# DPA110_to-264v4-upravena.net
KiCad netlist of a schematic drawn in EAGLE
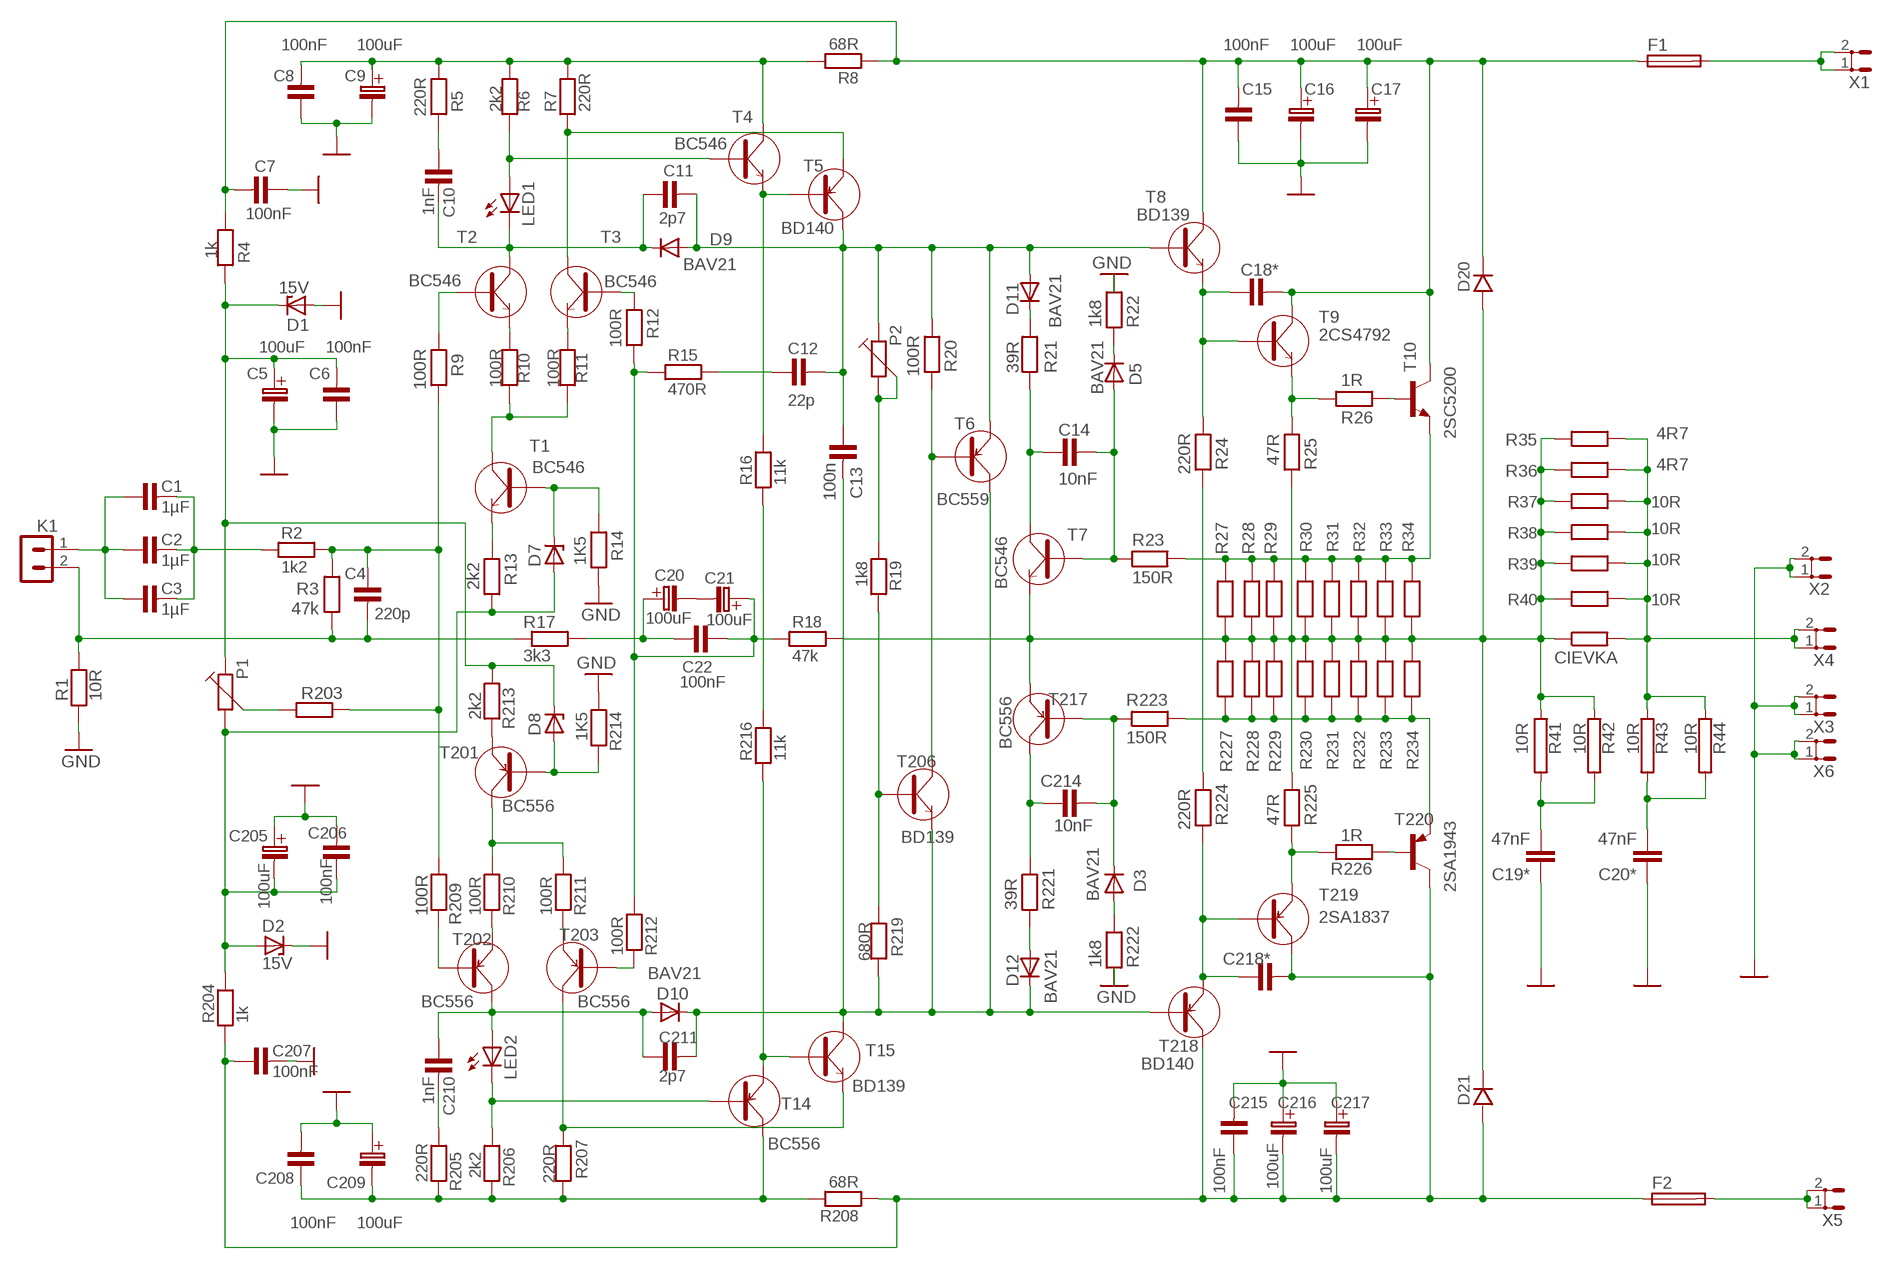
[diagram p0: schematic, sheet 1]

(export (version "E")
  (design (tool "Eeschema 10.0.6"))
  (components
    (comp (ref "C1")
      (value "1µF")
      (footprint "eagle-import:C-5")
      (libsource (lib "eagle-import") (part "C-KERAMIK_5"))
    )
    (comp (ref "C2")
      (value "1µF")
      (footprint "eagle-import:C-5")
      (libsource (lib "eagle-import") (part "C-KERAMIK_5"))
    )
    (comp (ref "C3")
      (value "1µF")
      (footprint "eagle-import:C-5")
      (libsource (lib "eagle-import") (part "C-KERAMIK_5"))
    )
    (comp (ref "C4")
      (value "220p")
      (footprint "eagle-import:C-5")
      (libsource (lib "eagle-import") (part "C-KERAMIK_5"))
    )
    (comp (ref "C5")
      (value "100uF")
      (footprint "eagle-import:C-EL_2")
      (libsource (lib "eagle-import") (part "C-ELEKTROLYT_2"))
    )
    (comp (ref "C6")
      (value "100nF")
      (footprint "eagle-import:C-5")
      (libsource (lib "eagle-import") (part "C-KERAMIK_5"))
    )
    (comp (ref "C7")
      (value "100nF")
      (footprint "eagle-import:C-5")
      (libsource (lib "eagle-import") (part "C-KERAMIK_5"))
    )
    (comp (ref "C8")
      (value "100nF")
      (footprint "eagle-import:C-5")
      (libsource (lib "eagle-import") (part "C-KERAMIK_5"))
    )
    (comp (ref "C9")
      (value "100uF")
      (footprint "eagle-import:C-EL_3,5")
      (libsource (lib "eagle-import") (part "C-ELEKTROLYT_3,5"))
    )
    (comp (ref "C10")
      (value "1nF")
      (footprint "eagle-import:C-5")
      (libsource (lib "eagle-import") (part "#PaJa_30_C-KERAMIK_5"))
    )
    (comp (ref "C11")
      (value "2p7")
      (footprint "eagle-import:C-5")
      (libsource (lib "eagle-import") (part "C-KERAMIK_5"))
    )
    (comp (ref "C12")
      (value "22p")
      (footprint "eagle-import:C-5")
      (libsource (lib "eagle-import") (part "C-KERAMIK_5"))
    )
    (comp (ref "C13")
      (value "100n")
      (footprint "eagle-import:C-5")
      (libsource (lib "eagle-import") (part "C-KERAMIK_5"))
    )
    (comp (ref "C14")
      (value "10nF")
      (footprint "eagle-import:C-5")
      (libsource (lib "eagle-import") (part "C-KERAMIK_5"))
    )
    (comp (ref "C15")
      (value "100nF")
      (footprint "eagle-import:C-5")
      (libsource (lib "eagle-import") (part "C-KERAMIK_5"))
    )
    (comp (ref "C16")
      (value "100uF")
      (footprint "eagle-import:C-EL_3,5")
      (libsource (lib "eagle-import") (part "C-ELEKTROLYT_3,5"))
    )
    (comp (ref "C17")
      (value "100uF")
      (footprint "eagle-import:C-EL_3,5")
      (libsource (lib "eagle-import") (part "C-ELEKTROLYT_3,5"))
    )
    (comp (ref "C18*")
      (value "C-KERAMIK_5")
      (footprint "eagle-import:C-5")
      (libsource (lib "eagle-import") (part "C-KERAMIK_5"))
    )
    (comp (ref "C19*")
      (value "47nF")
      (footprint "eagle-import:C150-054X183")
      (libsource (lib "eagle-import") (part "C-EU150-054X183"))
    )
    (comp (ref "C20")
      (value "100uF")
      (footprint "eagle-import:C-EL_3,5")
      (libsource (lib "eagle-import") (part "C-ELEKTROLYT_3,5"))
    )
    (comp (ref "C20*")
      (value "47nF")
      (footprint "eagle-import:C150-054X183")
      (libsource (lib "eagle-import") (part "C-EU150-054X183"))
    )
    (comp (ref "C21")
      (value "100uF")
      (footprint "eagle-import:C-EL_3,5")
      (libsource (lib "eagle-import") (part "C-ELEKTROLYT_3,5"))
    )
    (comp (ref "C22")
      (value "100nF")
      (footprint "eagle-import:C-5")
      (libsource (lib "eagle-import") (part "C-KERAMIK_5"))
    )
    (comp (ref "C205")
      (value "100uF")
      (footprint "eagle-import:C-EL_2")
      (libsource (lib "eagle-import") (part "C-ELEKTROLYT_2"))
    )
    (comp (ref "C206")
      (value "100nF")
      (footprint "eagle-import:C-5")
      (libsource (lib "eagle-import") (part "C-KERAMIK_5"))
    )
    (comp (ref "C207")
      (value "100nF")
      (footprint "eagle-import:C-5")
      (libsource (lib "eagle-import") (part "C-KERAMIK_5"))
    )
    (comp (ref "C208")
      (value "100nF")
      (footprint "eagle-import:C-5")
      (libsource (lib "eagle-import") (part "C-KERAMIK_5"))
    )
    (comp (ref "C209")
      (value "100uF")
      (footprint "eagle-import:C-EL_3,5")
      (libsource (lib "eagle-import") (part "C-ELEKTROLYT_3,5"))
    )
    (comp (ref "C210")
      (value "1nF")
      (footprint "eagle-import:C-5")
      (libsource (lib "eagle-import") (part "#PaJa_30_C-KERAMIK_5"))
    )
    (comp (ref "C211")
      (value "2p7")
      (footprint "eagle-import:C-5")
      (libsource (lib "eagle-import") (part "C-KERAMIK_5"))
    )
    (comp (ref "C214")
      (value "10nF")
      (footprint "eagle-import:C-5")
      (libsource (lib "eagle-import") (part "C-KERAMIK_5"))
    )
    (comp (ref "C215")
      (value "100nF")
      (footprint "eagle-import:C-5")
      (libsource (lib "eagle-import") (part "C-KERAMIK_5"))
    )
    (comp (ref "C216")
      (value "100uF")
      (footprint "eagle-import:C-EL_3,5")
      (libsource (lib "eagle-import") (part "C-ELEKTROLYT_3,5"))
    )
    (comp (ref "C217")
      (value "100uF")
      (footprint "eagle-import:C-EL_3,5")
      (libsource (lib "eagle-import") (part "C-ELEKTROLYT_3,5"))
    )
    (comp (ref "C218*")
      (value "C-KERAMIK_5")
      (footprint "eagle-import:C-5")
      (libsource (lib "eagle-import") (part "C-KERAMIK_5"))
    )
    (comp (ref "CIEVKA")
      (value "10R")
      (footprint "eagle-import:0617_22")
      (libsource (lib "eagle-import") (part "R-EU_0617/22"))
    )
    (comp (ref "D1")
      (value "15V")
      (footprint "eagle-import:SOD81")
      (libsource (lib "eagle-import") (part "BZD23"))
    )
    (comp (ref "D2")
      (value "15V")
      (footprint "eagle-import:SOD81")
      (libsource (lib "eagle-import") (part "BZD23"))
    )
    (comp (ref "D3")
      (value "BAV21")
      (footprint "eagle-import:DO35-10")
      (libsource (lib "eagle-import") (part "BAV21"))
    )
    (comp (ref "D5")
      (value "BAV21")
      (footprint "eagle-import:DO35-10")
      (libsource (lib "eagle-import") (part "BAV21"))
    )
    (comp (ref "D7")
      (value "BZX55")
      (footprint "eagle-import:DO35Z10")
      (libsource (lib "eagle-import") (part "BZX55"))
    )
    (comp (ref "D8")
      (value "BZX55")
      (footprint "eagle-import:DO35Z10")
      (libsource (lib "eagle-import") (part "BZX55"))
    )
    (comp (ref "D9")
      (value "BAV21")
      (footprint "eagle-import:DO35-10")
      (libsource (lib "eagle-import") (part "BAV21"))
    )
    (comp (ref "D10")
      (value "BAV21")
      (footprint "eagle-import:DO35-10")
      (libsource (lib "eagle-import") (part "BAV21"))
    )
    (comp (ref "D11")
      (value "BAV21")
      (footprint "eagle-import:DO35-10")
      (libsource (lib "eagle-import") (part "BAV21"))
    )
    (comp (ref "D12")
      (value "BAV21")
      (footprint "eagle-import:DO35-10")
      (libsource (lib "eagle-import") (part "BAV21"))
    )
    (comp (ref "D20")
      (value "D_10")
      (footprint "eagle-import:DO41")
      (libsource (lib "eagle-import") (part "D_10"))
    )
    (comp (ref "D21")
      (value "D_10")
      (footprint "eagle-import:DO41")
      (libsource (lib "eagle-import") (part "D_10"))
    )
    (comp (ref "F1")
      (value "SH22,5A")
      (footprint "eagle-import:SH22,5A")
      (libsource (lib "eagle-import") (part "SH22,5A"))
    )
    (comp (ref "F2")
      (value "SH22,5A")
      (footprint "eagle-import:SH22,5A")
      (libsource (lib "eagle-import") (part "SH22,5A"))
    )
    (comp (ref "K1")
      (value "PSH02-02P")
      (footprint "eagle-import:PSH02-02P")
      (libsource (lib "eagle-import") (part "PSH02-02P"))
    )
    (comp (ref "LED1")
      (value "LED5MM")
      (footprint "eagle-import:LED5MM")
      (libsource (lib "eagle-import") (part "LED5MM"))
    )
    (comp (ref "LED2")
      (value "LED5MM")
      (footprint "eagle-import:LED5MM")
      (libsource (lib "eagle-import") (part "LED5MM"))
    )
    (comp (ref "P1")
      (value "TRIMR64Y")
      (footprint "eagle-import:64Y")
      (libsource (lib "eagle-import") (part "TRIMR64Y"))
    )
    (comp (ref "P2")
      (value "TRIMR64Y")
      (footprint "eagle-import:64Y")
      (libsource (lib "eagle-import") (part "TRIMR64Y"))
    )
    (comp (ref "R1")
      (value "10R")
      (footprint "eagle-import:R-10")
      (libsource (lib "eagle-import") (part "#PaJa_30_R_10"))
    )
    (comp (ref "R2")
      (value "1k2")
      (footprint "eagle-import:R-10")
      (libsource (lib "eagle-import") (part "#PaJa_30_R_10"))
    )
    (comp (ref "R3")
      (value "47k")
      (footprint "eagle-import:R-10")
      (libsource (lib "eagle-import") (part "#PaJa_30_R_10"))
    )
    (comp (ref "R4")
      (value "1k")
      (footprint "eagle-import:R-10")
      (libsource (lib "eagle-import") (part "R_10"))
    )
    (comp (ref "R5")
      (value "220R")
      (footprint "eagle-import:R-10")
      (libsource (lib "eagle-import") (part "#PaJa_30_R_10"))
    )
    (comp (ref "R6")
      (value "2k2")
      (footprint "eagle-import:R-10")
      (libsource (lib "eagle-import") (part "#PaJa_30_R_10"))
    )
    (comp (ref "R7")
      (value "220R")
      (footprint "eagle-import:R-10")
      (libsource (lib "eagle-import") (part "#PaJa_30_R_10"))
    )
    (comp (ref "R8")
      (value "68R")
      (footprint "eagle-import:R-10")
      (libsource (lib "eagle-import") (part "#PaJa_30_R_10"))
    )
    (comp (ref "R9")
      (value "100R")
      (footprint "eagle-import:R-10")
      (libsource (lib "eagle-import") (part "#PaJa_30_R_10"))
    )
    (comp (ref "R10")
      (value "100R")
      (footprint "eagle-import:R-7,5")
      (libsource (lib "eagle-import") (part "R_7,5"))
    )
    (comp (ref "R11")
      (value "100R")
      (footprint "eagle-import:R-7,5")
      (libsource (lib "eagle-import") (part "R_7,5"))
    )
    (comp (ref "R12")
      (value "100R")
      (footprint "eagle-import:R-10")
      (libsource (lib "eagle-import") (part "#PaJa_30_R_10"))
    )
    (comp (ref "R13")
      (value "2k2")
      (footprint "eagle-import:R-10")
      (libsource (lib "eagle-import") (part "#PaJa_30_R_10"))
    )
    (comp (ref "R14")
      (value "1K5")
      (footprint "eagle-import:R-10")
      (libsource (lib "eagle-import") (part "#PaJa_30_R_10"))
    )
    (comp (ref "R15")
      (value "470R")
      (footprint "eagle-import:R-10")
      (libsource (lib "eagle-import") (part "R_10"))
    )
    (comp (ref "R16")
      (value "11k")
      (footprint "eagle-import:R-10")
      (libsource (lib "eagle-import") (part "R_10"))
    )
    (comp (ref "R17")
      (value "3k3")
      (footprint "eagle-import:R-10")
      (libsource (lib "eagle-import") (part "#PaJa_30_R_10"))
    )
    (comp (ref "R18")
      (value "47k")
      (footprint "eagle-import:R-10")
      (libsource (lib "eagle-import") (part "#PaJa_30_R_10"))
    )
    (comp (ref "R19")
      (value "1k8")
      (footprint "eagle-import:R-10")
      (libsource (lib "eagle-import") (part "#PaJa_30_R_10"))
    )
    (comp (ref "R20")
      (value "100R")
      (footprint "eagle-import:R-10")
      (libsource (lib "eagle-import") (part "R_10"))
    )
    (comp (ref "R21")
      (value "39R")
      (footprint "eagle-import:R-10")
      (libsource (lib "eagle-import") (part "#PaJa_30_R_10"))
    )
    (comp (ref "R22")
      (value "1k8")
      (footprint "eagle-import:R-10")
      (libsource (lib "eagle-import") (part "R_10"))
    )
    (comp (ref "R23")
      (value "150R")
      (footprint "eagle-import:R-10")
      (libsource (lib "eagle-import") (part "R_10"))
    )
    (comp (ref "R24")
      (value "220R")
      (footprint "eagle-import:R-10")
      (libsource (lib "eagle-import") (part "R_10"))
    )
    (comp (ref "R25")
      (value "47R")
      (footprint "eagle-import:R-10")
      (libsource (lib "eagle-import") (part "R_10"))
    )
    (comp (ref "R26")
      (value "1R")
      (footprint "eagle-import:R-10")
      (libsource (lib "eagle-import") (part "R_10"))
    )
    (comp (ref "R27")
      (value "R__2W")
      (footprint "eagle-import:R-_2W")
      (libsource (lib "eagle-import") (part "R__2W"))
    )
    (comp (ref "R28")
      (value "R__2W")
      (footprint "eagle-import:R-_2W")
      (libsource (lib "eagle-import") (part "R__2W"))
    )
    (comp (ref "R29")
      (value "R__2W")
      (footprint "eagle-import:R-_2W")
      (libsource (lib "eagle-import") (part "R__2W"))
    )
    (comp (ref "R30")
      (value "R_10")
      (footprint "eagle-import:R-10")
      (libsource (lib "eagle-import") (part "R_10"))
    )
    (comp (ref "R31")
      (value "R_10")
      (footprint "eagle-import:R-10")
      (libsource (lib "eagle-import") (part "R_10"))
    )
    (comp (ref "R32")
      (value "R_10")
      (footprint "eagle-import:R-10")
      (libsource (lib "eagle-import") (part "R_10"))
    )
    (comp (ref "R33")
      (value "R_10")
      (footprint "eagle-import:R-10")
      (libsource (lib "eagle-import") (part "R_10"))
    )
    (comp (ref "R34")
      (value "R_10")
      (footprint "eagle-import:R-10")
      (libsource (lib "eagle-import") (part "R_10"))
    )
    (comp (ref "R35")
      (value "4R7")
      (footprint "eagle-import:R-_2W")
      (libsource (lib "eagle-import") (part "R__2W"))
    )
    (comp (ref "R36")
      (value "4R7")
      (footprint "eagle-import:R-_2W")
      (libsource (lib "eagle-import") (part "R__2W"))
    )
    (comp (ref "R37")
      (value "10R")
      (footprint "eagle-import:R-10")
      (libsource (lib "eagle-import") (part "R_10"))
    )
    (comp (ref "R38")
      (value "10R")
      (footprint "eagle-import:R-10")
      (libsource (lib "eagle-import") (part "R_10"))
    )
    (comp (ref "R39")
      (value "10R")
      (footprint "eagle-import:R-10")
      (libsource (lib "eagle-import") (part "R_10"))
    )
    (comp (ref "R40")
      (value "10R")
      (footprint "eagle-import:R-10")
      (libsource (lib "eagle-import") (part "R_10"))
    )
    (comp (ref "R41")
      (value "10R")
      (footprint "eagle-import:AC01")
      (libsource (lib "eagle-import") (part "RAC01"))
    )
    (comp (ref "R42")
      (value "10R")
      (footprint "eagle-import:AC01")
      (libsource (lib "eagle-import") (part "RAC01"))
    )
    (comp (ref "R43")
      (value "10R")
      (footprint "eagle-import:AC01")
      (libsource (lib "eagle-import") (part "RAC01"))
    )
    (comp (ref "R44")
      (value "10R")
      (footprint "eagle-import:AC01")
      (libsource (lib "eagle-import") (part "RAC01"))
    )
    (comp (ref "R203")
      (value "R_10")
      (footprint "eagle-import:R-10")
      (libsource (lib "eagle-import") (part "#PaJa_30_R_10"))
    )
    (comp (ref "R204")
      (value "1k")
      (footprint "eagle-import:R-10")
      (libsource (lib "eagle-import") (part "R_10"))
    )
    (comp (ref "R205")
      (value "220R")
      (footprint "eagle-import:R-10")
      (libsource (lib "eagle-import") (part "#PaJa_30_R_10"))
    )
    (comp (ref "R206")
      (value "2k2")
      (footprint "eagle-import:R-10")
      (libsource (lib "eagle-import") (part "#PaJa_30_R_10"))
    )
    (comp (ref "R207")
      (value "220R")
      (footprint "eagle-import:R-10")
      (libsource (lib "eagle-import") (part "#PaJa_30_R_10"))
    )
    (comp (ref "R208")
      (value "68R")
      (footprint "eagle-import:R-10")
      (libsource (lib "eagle-import") (part "#PaJa_30_R_10"))
    )
    (comp (ref "R209")
      (value "100R")
      (footprint "eagle-import:R-10")
      (libsource (lib "eagle-import") (part "R_10"))
    )
    (comp (ref "R210")
      (value "100R")
      (footprint "eagle-import:R-7,5")
      (libsource (lib "eagle-import") (part "R_7,5"))
    )
    (comp (ref "R211")
      (value "100R")
      (footprint "eagle-import:R-7,5")
      (libsource (lib "eagle-import") (part "R_7,5"))
    )
    (comp (ref "R212")
      (value "100R")
      (footprint "eagle-import:R-10")
      (libsource (lib "eagle-import") (part "#PaJa_30_R_10"))
    )
    (comp (ref "R213")
      (value "2k2")
      (footprint "eagle-import:R-10")
      (libsource (lib "eagle-import") (part "#PaJa_30_R_10"))
    )
    (comp (ref "R214")
      (value "1K5")
      (footprint "eagle-import:R-10")
      (libsource (lib "eagle-import") (part "#PaJa_30_R_10"))
    )
    (comp (ref "R216")
      (value "11k")
      (footprint "eagle-import:R-10")
      (libsource (lib "eagle-import") (part "#PaJa_30_R_10"))
    )
    (comp (ref "R219")
      (value "680R")
      (footprint "eagle-import:R-10")
      (libsource (lib "eagle-import") (part "#PaJa_30_R_10"))
    )
    (comp (ref "R221")
      (value "39R")
      (footprint "eagle-import:R-10")
      (libsource (lib "eagle-import") (part "#PaJa_30_R_10"))
    )
    (comp (ref "R222")
      (value "1k8")
      (footprint "eagle-import:R-10")
      (libsource (lib "eagle-import") (part "R_10"))
    )
    (comp (ref "R223")
      (value "150R")
      (footprint "eagle-import:R-10")
      (libsource (lib "eagle-import") (part "R_10"))
    )
    (comp (ref "R224")
      (value "220R")
      (footprint "eagle-import:R-10")
      (libsource (lib "eagle-import") (part "R_10"))
    )
    (comp (ref "R225")
      (value "47R")
      (footprint "eagle-import:R-10")
      (libsource (lib "eagle-import") (part "R_10"))
    )
    (comp (ref "R226")
      (value "1R")
      (footprint "eagle-import:R-10")
      (libsource (lib "eagle-import") (part "R_10"))
    )
    (comp (ref "R227")
      (value "R__2W")
      (footprint "eagle-import:R-_2W")
      (libsource (lib "eagle-import") (part "R__2W"))
    )
    (comp (ref "R228")
      (value "R__2W")
      (footprint "eagle-import:R-_2W")
      (libsource (lib "eagle-import") (part "R__2W"))
    )
    (comp (ref "R229")
      (value "R__2W")
      (footprint "eagle-import:R-_2W")
      (libsource (lib "eagle-import") (part "R__2W"))
    )
    (comp (ref "R230")
      (value "R_10")
      (footprint "eagle-import:R-10")
      (libsource (lib "eagle-import") (part "R_10"))
    )
    (comp (ref "R231")
      (value "R_10")
      (footprint "eagle-import:R-10")
      (libsource (lib "eagle-import") (part "R_10"))
    )
    (comp (ref "R232")
      (value "R_10")
      (footprint "eagle-import:R-10")
      (libsource (lib "eagle-import") (part "R_10"))
    )
    (comp (ref "R233")
      (value "R_10")
      (footprint "eagle-import:R-10")
      (libsource (lib "eagle-import") (part "R_10"))
    )
    (comp (ref "R234")
      (value "R_10")
      (footprint "eagle-import:R-10")
      (libsource (lib "eagle-import") (part "R_10"))
    )
    (comp (ref "T1")
      (value "BC546")
      (footprint "eagle-import:TO-92")
      (libsource (lib "eagle-import") (part "BC546"))
    )
    (comp (ref "T2")
      (value "BC546")
      (footprint "eagle-import:TO-92")
      (libsource (lib "eagle-import") (part "BC546"))
    )
    (comp (ref "T3")
      (value "BC546")
      (footprint "eagle-import:TO-92")
      (libsource (lib "eagle-import") (part "BC546"))
    )
    (comp (ref "T4")
      (value "BC546")
      (footprint "eagle-import:TO-92")
      (libsource (lib "eagle-import") (part "BC546"))
    )
    (comp (ref "T5")
      (value "BD140")
      (footprint "eagle-import:TO-126S")
      (libsource (lib "eagle-import") (part "BD140"))
    )
    (comp (ref "T6")
      (value "BC559")
      (footprint "eagle-import:TO-92")
      (libsource (lib "eagle-import") (part "BC559"))
    )
    (comp (ref "T7")
      (value "BC546")
      (footprint "eagle-import:TO-92")
      (libsource (lib "eagle-import") (part "BC546"))
    )
    (comp (ref "T8")
      (value "BD139")
      (footprint "eagle-import:TO-126")
      (libsource (lib "eagle-import") (part "BD139_LEZ"))
    )
    (comp (ref "T9")
      (value "2CS4792")
      (footprint "eagle-import:TO-220")
      (libsource (lib "eagle-import") (part "BD711_LEZ"))
    )
    (comp (ref "T10")
      (value "2SC5200")
      (footprint "eagle-import:TO-264")
      (libsource (lib "eagle-import") (part "2SC5200"))
    )
    (comp (ref "T14")
      (value "BC556")
      (footprint "eagle-import:TO-92")
      (libsource (lib "eagle-import") (part "BC556"))
    )
    (comp (ref "T15")
      (value "BD139")
      (footprint "eagle-import:TO-126S")
      (libsource (lib "eagle-import") (part "BD139"))
    )
    (comp (ref "T201")
      (value "BC556")
      (footprint "eagle-import:TO-92")
      (libsource (lib "eagle-import") (part "BC556"))
    )
    (comp (ref "T202")
      (value "BC556")
      (footprint "eagle-import:TO-92")
      (libsource (lib "eagle-import") (part "BC556"))
    )
    (comp (ref "T203")
      (value "BC556")
      (footprint "eagle-import:TO-92")
      (libsource (lib "eagle-import") (part "BC556"))
    )
    (comp (ref "T206")
      (value "BD139")
      (footprint "eagle-import:TO-126")
      (libsource (lib "eagle-import") (part "BD139_LEZ"))
    )
    (comp (ref "T217")
      (value "BC556")
      (footprint "eagle-import:TO-92")
      (libsource (lib "eagle-import") (part "BC556"))
    )
    (comp (ref "T218")
      (value "BD140")
      (footprint "eagle-import:TO-126")
      (libsource (lib "eagle-import") (part "BD140_LEZ"))
    )
    (comp (ref "T219")
      (value "2SA1837")
      (footprint "eagle-import:TO-220")
      (libsource (lib "eagle-import") (part "BD912_LEZ"))
    )
    (comp (ref "T220")
      (value "2SA1943")
      (footprint "eagle-import:TO-264")
      (libsource (lib "eagle-import") (part "2SA1943"))
    )
    (comp (ref "X1")
      (value "ST4,8")
      (footprint "eagle-import:ST4,8")
      (libsource (lib "eagle-import") (part "ST4,8"))
    )
    (comp (ref "X2")
      (value "ST4,8")
      (footprint "eagle-import:ST4,8")
      (libsource (lib "eagle-import") (part "ST4,8"))
    )
    (comp (ref "X3")
      (value "ST4,8")
      (footprint "eagle-import:ST4,8")
      (libsource (lib "eagle-import") (part "ST4,8"))
    )
    (comp (ref "X4")
      (value "ST4,8")
      (footprint "eagle-import:ST4,8")
      (libsource (lib "eagle-import") (part "ST4,8"))
    )
    (comp (ref "X5")
      (value "ST4,8")
      (footprint "eagle-import:ST4,8")
      (libsource (lib "eagle-import") (part "ST4,8"))
    )
    (comp (ref "X6")
      (value "ST4,8")
      (footprint "eagle-import:ST4,8")
      (libsource (lib "eagle-import") (part "ST4,8"))
    )
  )
  (nets
    (net (code "1") (name "GND") (class "Default")
      (node (ref "C15") (pin "1") (pinfunction "1_1") (pintype "passive"))
      (node (ref "C16") (pin "C-") (pinfunction "C_EL-_C-") (pintype "passive"))
      (node (ref "C17") (pin "C-") (pinfunction "C_EL-_C-") (pintype "passive"))
      (node (ref "C19*") (pin "1") (pinfunction "1_1") (pintype "passive"))
      (node (ref "C20*") (pin "1") (pinfunction "1_1") (pintype "passive"))
      (node (ref "C205") (pin "C+") (pinfunction "C_EL+_C+") (pintype "passive"))
      (node (ref "C206") (pin "2") (pinfunction "2_2") (pintype "passive"))
      (node (ref "C207") (pin "2") (pinfunction "2_2") (pintype "passive"))
      (node (ref "C208") (pin "2") (pinfunction "2_2") (pintype "passive"))
      (node (ref "C209") (pin "C+") (pinfunction "C_EL+_C+") (pintype "passive"))
      (node (ref "C215") (pin "2") (pinfunction "2_2") (pintype "passive"))
      (node (ref "C216") (pin "C+") (pinfunction "C_EL+_C+") (pintype "passive"))
      (node (ref "C217") (pin "C+") (pinfunction "C_EL+_C+") (pintype "passive"))
      (node (ref "C5") (pin "C-") (pinfunction "C_EL-_C-") (pintype "passive"))
      (node (ref "C6") (pin "1") (pinfunction "1_1") (pintype "passive"))
      (node (ref "C7") (pin "1") (pinfunction "1_1") (pintype "passive"))
      (node (ref "C8") (pin "1") (pinfunction "1_1") (pintype "passive"))
      (node (ref "C9") (pin "C-") (pinfunction "C_EL-_C-") (pintype "passive"))
      (node (ref "D1") (pin "A") (pinfunction "A_A") (pintype "passive"))
      (node (ref "D2") (pin "C") (pinfunction "C_C") (pintype "passive"))
      (node (ref "R1") (pin "1") (pinfunction "1_1") (pintype "passive"))
      (node (ref "R14") (pin "1") (pinfunction "1_1") (pintype "passive"))
      (node (ref "R214") (pin "1") (pinfunction "1_1") (pintype "passive"))
      (node (ref "R22") (pin "2") (pinfunction "2_2") (pintype "passive"))
      (node (ref "R222") (pin "1") (pinfunction "1_1") (pintype "passive"))
      (node (ref "X2") (pin "1") (pinfunction "1_1") (pintype "passive"))
      (node (ref "X2") (pin "2") (pinfunction "2_2") (pintype "passive"))
      (node (ref "X3") (pin "1") (pinfunction "1_1") (pintype "passive"))
      (node (ref "X3") (pin "2") (pinfunction "2_2") (pintype "passive"))
      (node (ref "X6") (pin "1") (pinfunction "1_1") (pintype "passive"))
      (node (ref "X6") (pin "2") (pinfunction "2_2") (pintype "passive"))
    )
    (net (code "2") (name "Net-(C1-Pad1)") (class "Default")
      (node (ref "C1") (pin "1") (pinfunction "1_1") (pintype "passive"))
      (node (ref "C2") (pin "1") (pinfunction "1_1") (pintype "passive"))
      (node (ref "C3") (pin "1") (pinfunction "1_1") (pintype "passive"))
      (node (ref "K1") (pin "1") (pinfunction "1_1") (pintype "passive"))
    )
    (net (code "3") (name "Net-(C1-Pad2)") (class "Default")
      (node (ref "C1") (pin "2") (pinfunction "2_2") (pintype "passive"))
      (node (ref "C2") (pin "2") (pinfunction "2_2") (pintype "passive"))
      (node (ref "C3") (pin "2") (pinfunction "2_2") (pintype "passive"))
      (node (ref "R2") (pin "1") (pinfunction "1_1") (pintype "passive"))
    )
    (net (code "4") (name "Net-(C4-Pad1)") (class "Default")
      (node (ref "C4") (pin "1") (pinfunction "1_1") (pintype "passive"))
      (node (ref "R2") (pin "2") (pinfunction "2_2") (pintype "passive"))
      (node (ref "R203") (pin "2") (pinfunction "2_2") (pintype "passive"))
      (node (ref "R209") (pin "1") (pinfunction "1_1") (pintype "passive"))
      (node (ref "R3") (pin "2") (pinfunction "2_2") (pintype "passive"))
      (node (ref "R9") (pin "1") (pinfunction "1_1") (pintype "passive"))
    )
    (net (code "5") (name "Net-(C4-Pad2)") (class "Default")
      (node (ref "C4") (pin "2") (pinfunction "2_2") (pintype "passive"))
      (node (ref "K1") (pin "2") (pinfunction "2_2") (pintype "passive"))
      (node (ref "R1") (pin "2") (pinfunction "2_2") (pintype "passive"))
      (node (ref "R17") (pin "1") (pinfunction "1_1") (pintype "passive"))
      (node (ref "R3") (pin "1") (pinfunction "1_1") (pintype "passive"))
    )
    (net (code "6") (name "Net-(C5-C_EL+)") (class "Default")
      (node (ref "C5") (pin "C+") (pinfunction "C_EL+_C+") (pintype "passive"))
      (node (ref "C6") (pin "2") (pinfunction "2_2") (pintype "passive"))
      (node (ref "D1") (pin "C") (pinfunction "C_C") (pintype "passive"))
      (node (ref "D8") (pin "C") (pinfunction "C_C") (pintype "passive"))
      (node (ref "P1") (pin "1") (pinfunction "1_1") (pintype "passive"))
      (node (ref "R213") (pin "1") (pinfunction "1_1") (pintype "passive"))
      (node (ref "R4") (pin "1") (pinfunction "1_1") (pintype "passive"))
    )
    (net (code "7") (name "Net-(C10-Pad1)") (class "Default")
      (node (ref "C10") (pin "1") (pinfunction "1_1") (pintype "passive"))
      (node (ref "R5") (pin "1") (pinfunction "1_1") (pintype "passive"))
    )
    (net (code "8") (name "Net-(C12-Pad1)") (class "Default")
      (node (ref "C12") (pin "1") (pinfunction "1_1") (pintype "passive"))
      (node (ref "R15") (pin "2") (pinfunction "2_2") (pintype "passive"))
    )
    (net (code "9") (name "Net-(C16-C_EL+)") (class "Default")
      (node (ref "C15") (pin "2") (pinfunction "2_2") (pintype "passive"))
      (node (ref "C16") (pin "C+") (pinfunction "C_EL+_C+") (pintype "passive"))
      (node (ref "C17") (pin "C+") (pinfunction "C_EL+_C+") (pintype "passive"))
      (node (ref "C18*") (pin "2") (pinfunction "2_2") (pintype "passive"))
      (node (ref "C7") (pin "2") (pinfunction "2_2") (pintype "passive"))
      (node (ref "D20") (pin "K") (pinfunction "K_K") (pintype "passive"))
      (node (ref "F1") (pin "1") (pinfunction "1_1") (pintype "passive"))
      (node (ref "R4") (pin "2") (pinfunction "2_2") (pintype "passive"))
      (node (ref "R8") (pin "1") (pinfunction "1_1") (pintype "passive"))
      (node (ref "T10") (pin "C") (pinfunction "C_C") (pintype "passive"))
      (node (ref "T8") (pin "2") (pinfunction "C_2") (pintype "passive"))
      (node (ref "T9") (pin "2") (pinfunction "C_2") (pintype "passive"))
    )
    (net (code "10") (name "Net-(C19*-Pad2)") (class "Default")
      (node (ref "C19*") (pin "2") (pinfunction "2_2") (pintype "passive"))
      (node (ref "R41") (pin "2") (pinfunction "2_2") (pintype "passive"))
      (node (ref "R42") (pin "2") (pinfunction "2_2") (pintype "passive"))
    )
    (net (code "11") (name "Net-(C20*-Pad2)") (class "Default")
      (node (ref "C20*") (pin "2") (pinfunction "2_2") (pintype "passive"))
      (node (ref "R43") (pin "2") (pinfunction "2_2") (pintype "passive"))
      (node (ref "R44") (pin "2") (pinfunction "2_2") (pintype "passive"))
    )
    (net (code "12") (name "Net-(C20-C_EL+)") (class "Default")
      (node (ref "C20") (pin "C+") (pinfunction "C_EL+_C+") (pintype "passive"))
      (node (ref "C22") (pin "2") (pinfunction "2_2") (pintype "passive"))
      (node (ref "R17") (pin "2") (pinfunction "2_2") (pintype "passive"))
    )
    (net (code "13") (name "Net-(C20-C_EL-)") (class "Default")
      (node (ref "C20") (pin "C-") (pinfunction "C_EL-_C-") (pintype "passive"))
      (node (ref "C21") (pin "C-") (pinfunction "C_EL-_C-") (pintype "passive"))
    )
    (net (code "14") (name "Net-(C21-C_EL+)") (class "Default")
      (node (ref "C21") (pin "C+") (pinfunction "C_EL+_C+") (pintype "passive"))
      (node (ref "C22") (pin "1") (pinfunction "1_1") (pintype "passive"))
      (node (ref "R12") (pin "1") (pinfunction "1_1") (pintype "passive"))
      (node (ref "R15") (pin "1") (pinfunction "1_1") (pintype "passive"))
      (node (ref "R18") (pin "1") (pinfunction "1_1") (pintype "passive"))
      (node (ref "R212") (pin "1") (pinfunction "1_1") (pintype "passive"))
    )
    (net (code "15") (name "Net-(C205-C_EL-)") (class "Default")
      (node (ref "C205") (pin "C-") (pinfunction "C_EL-_C-") (pintype "passive"))
      (node (ref "C206") (pin "1") (pinfunction "1_1") (pintype "passive"))
      (node (ref "D2") (pin "A") (pinfunction "A_A") (pintype "passive"))
      (node (ref "D7") (pin "A") (pinfunction "A_A") (pintype "passive"))
      (node (ref "P1") (pin "2") (pinfunction "2_2") (pintype "passive"))
      (node (ref "R13") (pin "1") (pinfunction "1_1") (pintype "passive"))
      (node (ref "R204") (pin "2") (pinfunction "2_2") (pintype "passive"))
    )
    (net (code "16") (name "Net-(C209-C_EL-)") (class "Default")
      (node (ref "C208") (pin "1") (pinfunction "1_1") (pintype "passive"))
      (node (ref "C209") (pin "C-") (pinfunction "C_EL-_C-") (pintype "passive"))
      (node (ref "R205") (pin "2") (pinfunction "2_2") (pintype "passive"))
      (node (ref "R206") (pin "2") (pinfunction "2_2") (pintype "passive"))
      (node (ref "R207") (pin "1") (pinfunction "1_1") (pintype "passive"))
      (node (ref "R208") (pin "2") (pinfunction "2_2") (pintype "passive"))
      (node (ref "T14") (pin "1") (pinfunction "C_1") (pintype "passive"))
    )
    (net (code "17") (name "Net-(C210-Pad2)") (class "Default")
      (node (ref "C210") (pin "2") (pinfunction "2_2") (pintype "passive"))
      (node (ref "R205") (pin "1") (pinfunction "1_1") (pintype "passive"))
    )
    (net (code "18") (name "Net-(C216-C_EL-)") (class "Default")
      (node (ref "C207") (pin "1") (pinfunction "1_1") (pintype "passive"))
      (node (ref "C215") (pin "1") (pinfunction "1_1") (pintype "passive"))
      (node (ref "C216") (pin "C-") (pinfunction "C_EL-_C-") (pintype "passive"))
      (node (ref "C217") (pin "C-") (pinfunction "C_EL-_C-") (pintype "passive"))
      (node (ref "C218*") (pin "2") (pinfunction "2_2") (pintype "passive"))
      (node (ref "D21") (pin "A") (pinfunction "A_A") (pintype "passive"))
      (node (ref "F2") (pin "1") (pinfunction "1_1") (pintype "passive"))
      (node (ref "R204") (pin "1") (pinfunction "1_1") (pintype "passive"))
      (node (ref "R208") (pin "1") (pinfunction "1_1") (pintype "passive"))
      (node (ref "T218") (pin "2") (pinfunction "C_2") (pintype "passive"))
      (node (ref "T219") (pin "2") (pinfunction "C_2") (pintype "passive"))
      (node (ref "T220") (pin "C") (pinfunction "C_C") (pintype "passive"))
    )
    (net (code "19") (name "Net-(CIEVKA-Pad2)") (class "Default")
      (node (ref "CIEVKA") (pin "2") (pinfunction "2_2") (pintype "passive"))
      (node (ref "R35") (pin "2") (pinfunction "2_2") (pintype "passive"))
      (node (ref "R36") (pin "2") (pinfunction "2_2") (pintype "passive"))
      (node (ref "R37") (pin "1") (pinfunction "1_1") (pintype "passive"))
      (node (ref "R38") (pin "1") (pinfunction "1_1") (pintype "passive"))
      (node (ref "R39") (pin "1") (pinfunction "1_1") (pintype "passive"))
      (node (ref "R40") (pin "1") (pinfunction "1_1") (pintype "passive"))
      (node (ref "R43") (pin "1") (pinfunction "1_1") (pintype "passive"))
      (node (ref "R44") (pin "1") (pinfunction "1_1") (pintype "passive"))
      (node (ref "X4") (pin "1") (pinfunction "1_1") (pintype "passive"))
      (node (ref "X4") (pin "2") (pinfunction "2_2") (pintype "passive"))
    )
    (net (code "20") (name "Net-(D3-PadA)") (class "Default")
      (node (ref "D3") (pin "A") (pinfunction "A_A") (pintype "passive"))
      (node (ref "R222") (pin "2") (pinfunction "2_2") (pintype "passive"))
    )
    (net (code "21") (name "Net-(D5-PadC)") (class "Default")
      (node (ref "D5") (pin "C") (pinfunction "C_C") (pintype "passive"))
      (node (ref "R22") (pin "1") (pinfunction "1_1") (pintype "passive"))
    )
    (net (code "22") (name "Net-(D11-PadC)") (class "Default")
      (node (ref "D11") (pin "C") (pinfunction "C_C") (pintype "passive"))
      (node (ref "R21") (pin "1") (pinfunction "1_1") (pintype "passive"))
    )
    (net (code "23") (name "Net-(D12-PadA)") (class "Default")
      (node (ref "D12") (pin "A") (pinfunction "A_A") (pintype "passive"))
      (node (ref "R221") (pin "1") (pinfunction "1_1") (pintype "passive"))
    )
    (net (code "24") (name "Net-(F1-Pad2)") (class "Default")
      (node (ref "F1") (pin "2") (pinfunction "2_2") (pintype "passive"))
      (node (ref "X1") (pin "1") (pinfunction "1_1") (pintype "passive"))
      (node (ref "X1") (pin "2") (pinfunction "2_2") (pintype "passive"))
    )
    (net (code "25") (name "Net-(F2-Pad2)") (class "Default")
      (node (ref "F2") (pin "2") (pinfunction "2_2") (pintype "passive"))
      (node (ref "X5") (pin "1") (pinfunction "1_1") (pintype "passive"))
      (node (ref "X5") (pin "2") (pinfunction "2_2") (pintype "passive"))
    )
    (net (code "26") (name "Net-(LED1-C)") (class "Default")
      (node (ref "C10") (pin "2") (pinfunction "2_2") (pintype "passive"))
      (node (ref "C11") (pin "1") (pinfunction "1_1") (pintype "passive"))
      (node (ref "D9") (pin "C") (pinfunction "C_C") (pintype "passive"))
      (node (ref "LED1") (pin "K") (pinfunction "C_K") (pintype "passive"))
      (node (ref "T2") (pin "1") (pinfunction "C_1") (pintype "passive"))
    )
    (net (code "27") (name "Net-(LED2-C)") (class "Default")
      (node (ref "LED2") (pin "K") (pinfunction "C_K") (pintype "passive"))
      (node (ref "R206") (pin "1") (pinfunction "1_1") (pintype "passive"))
      (node (ref "T14") (pin "2") (pinfunction "B_2") (pintype "passive"))
    )
    (net (code "28") (name "Net-(P1-Pad3)") (class "Default")
      (node (ref "P1") (pin "3") (pinfunction "3_3") (pintype "passive"))
      (node (ref "R203") (pin "1") (pinfunction "1_1") (pintype "passive"))
    )
    (net (code "29") (name "Net-(P2-Pad2)") (class "Default")
      (node (ref "P2") (pin "2") (pinfunction "2_2") (pintype "passive"))
      (node (ref "P2") (pin "3") (pinfunction "3_3") (pintype "passive"))
      (node (ref "R19") (pin "1") (pinfunction "1_1") (pintype "passive"))
    )
    (net (code "30") (name "Net-(R16-Pad1)") (class "Default")
      (node (ref "R16") (pin "1") (pinfunction "1_1") (pintype "passive"))
      (node (ref "R216") (pin "2") (pinfunction "2_2") (pintype "passive"))
    )
    (net (code "31") (name "Net-(R23-Pad2)") (class "Default")
      (node (ref "R23") (pin "2") (pinfunction "2_2") (pintype "passive"))
      (node (ref "R27") (pin "2") (pinfunction "2_2") (pintype "passive"))
      (node (ref "R28") (pin "2") (pinfunction "2_2") (pintype "passive"))
      (node (ref "R29") (pin "2") (pinfunction "2_2") (pintype "passive"))
      (node (ref "R30") (pin "2") (pinfunction "2_2") (pintype "passive"))
      (node (ref "R31") (pin "2") (pinfunction "2_2") (pintype "passive"))
      (node (ref "R32") (pin "2") (pinfunction "2_2") (pintype "passive"))
      (node (ref "R33") (pin "2") (pinfunction "2_2") (pintype "passive"))
      (node (ref "R34") (pin "2") (pinfunction "2_2") (pintype "passive"))
      (node (ref "T10") (pin "E") (pinfunction "E_E") (pintype "passive"))
    )
    (net (code "32") (name "Net-(R26-Pad2)") (class "Default")
      (node (ref "R26") (pin "2") (pinfunction "2_2") (pintype "passive"))
      (node (ref "T10") (pin "B") (pinfunction "B_B") (pintype "passive"))
    )
    (net (code "33") (name "Net-(R223-Pad1)") (class "Default")
      (node (ref "R223") (pin "1") (pinfunction "1_1") (pintype "passive"))
      (node (ref "R227") (pin "1") (pinfunction "1_1") (pintype "passive"))
      (node (ref "R228") (pin "1") (pinfunction "1_1") (pintype "passive"))
      (node (ref "R229") (pin "1") (pinfunction "1_1") (pintype "passive"))
      (node (ref "R230") (pin "1") (pinfunction "1_1") (pintype "passive"))
      (node (ref "R231") (pin "1") (pinfunction "1_1") (pintype "passive"))
      (node (ref "R232") (pin "1") (pinfunction "1_1") (pintype "passive"))
      (node (ref "R233") (pin "1") (pinfunction "1_1") (pintype "passive"))
      (node (ref "R234") (pin "1") (pinfunction "1_1") (pintype "passive"))
      (node (ref "T220") (pin "E") (pinfunction "E_E") (pintype "passive"))
    )
    (net (code "34") (name "Net-(R224-Pad2)") (class "Default")
      (node (ref "R224") (pin "2") (pinfunction "2_2") (pintype "passive"))
      (node (ref "R24") (pin "1") (pinfunction "1_1") (pintype "passive"))
    )
    (net (code "35") (name "Net-(R226-Pad1)") (class "Default")
      (node (ref "R226") (pin "1") (pinfunction "1_1") (pintype "passive"))
      (node (ref "T220") (pin "B") (pinfunction "B_B") (pintype "passive"))
    )
    (net (code "36") (name "Net-(T1-B)") (class "Default")
      (node (ref "D7") (pin "C") (pinfunction "C_C") (pintype "passive"))
      (node (ref "R14") (pin "2") (pinfunction "2_2") (pintype "passive"))
      (node (ref "T1") (pin "2") (pinfunction "B_2") (pintype "passive"))
    )
    (net (code "37") (name "Net-(T1-C)") (class "Default")
      (node (ref "R10") (pin "1") (pinfunction "1_1") (pintype "passive"))
      (node (ref "R11") (pin "1") (pinfunction "1_1") (pintype "passive"))
      (node (ref "T1") (pin "1") (pinfunction "C_1") (pintype "passive"))
    )
    (net (code "38") (name "Net-(T1-E)") (class "Default")
      (node (ref "R13") (pin "2") (pinfunction "2_2") (pintype "passive"))
      (node (ref "T1") (pin "3") (pinfunction "E_3") (pintype "passive"))
    )
    (net (code "39") (name "Net-(T2-B)") (class "Default")
      (node (ref "R9") (pin "2") (pinfunction "2_2") (pintype "passive"))
      (node (ref "T2") (pin "2") (pinfunction "B_2") (pintype "passive"))
    )
    (net (code "40") (name "Net-(T2-E)") (class "Default")
      (node (ref "R10") (pin "2") (pinfunction "2_2") (pintype "passive"))
      (node (ref "T2") (pin "3") (pinfunction "E_3") (pintype "passive"))
    )
    (net (code "41") (name "Net-(T3-B)") (class "Default")
      (node (ref "R12") (pin "2") (pinfunction "2_2") (pintype "passive"))
      (node (ref "T3") (pin "2") (pinfunction "B_2") (pintype "passive"))
    )
    (net (code "42") (name "Net-(T3-C)") (class "Default")
      (node (ref "R7") (pin "2") (pinfunction "2_2") (pintype "passive"))
      (node (ref "T3") (pin "1") (pinfunction "C_1") (pintype "passive"))
      (node (ref "T5") (pin "1") (pinfunction "E_1") (pintype "passive"))
    )
    (net (code "43") (name "Net-(T3-E)") (class "Default")
      (node (ref "R11") (pin "2") (pinfunction "2_2") (pintype "passive"))
      (node (ref "T3") (pin "3") (pinfunction "E_3") (pintype "passive"))
    )
    (net (code "44") (name "Net-(T4-B)") (class "Default")
      (node (ref "LED1") (pin "A") (pinfunction "A_A") (pintype "passive"))
      (node (ref "R6") (pin "1") (pinfunction "1_1") (pintype "passive"))
      (node (ref "T4") (pin "2") (pinfunction "B_2") (pintype "passive"))
    )
    (net (code "45") (name "Net-(T4-C)") (class "Default")
      (node (ref "C8") (pin "2") (pinfunction "2_2") (pintype "passive"))
      (node (ref "R5") (pin "2") (pinfunction "2_2") (pintype "passive"))
      (node (ref "R6") (pin "2") (pinfunction "2_2") (pintype "passive"))
      (node (ref "R7") (pin "1") (pinfunction "1_1") (pintype "passive"))
      (node (ref "R8") (pin "2") (pinfunction "2_2") (pintype "passive"))
      (node (ref "T4") (pin "1") (pinfunction "C_1") (pintype "passive"))
    )
    (net (code "46") (name "Net-(T4-E)") (class "Default")
      (node (ref "R16") (pin "2") (pinfunction "2_2") (pintype "passive"))
      (node (ref "T4") (pin "3") (pinfunction "E_3") (pintype "passive"))
      (node (ref "T5") (pin "3") (pinfunction "B_3") (pintype "passive"))
    )
    (net (code "47") (name "Net-(T5-C)") (class "Default")
      (node (ref "C11") (pin "2") (pinfunction "2_2") (pintype "passive"))
      (node (ref "C12") (pin "2") (pinfunction "2_2") (pintype "passive"))
      (node (ref "C13") (pin "1") (pinfunction "1_1") (pintype "passive"))
      (node (ref "D11") (pin "A") (pinfunction "A_A") (pintype "passive"))
      (node (ref "D9") (pin "A") (pinfunction "A_A") (pintype "passive"))
      (node (ref "P2") (pin "1") (pinfunction "1_1") (pintype "passive"))
      (node (ref "R20") (pin "2") (pinfunction "2_2") (pintype "passive"))
      (node (ref "T5") (pin "2") (pinfunction "C_2") (pintype "passive"))
      (node (ref "T6") (pin "3") (pinfunction "E_3") (pintype "passive"))
      (node (ref "T8") (pin "3") (pinfunction "B_3") (pintype "passive"))
    )
    (net (code "48") (name "Net-(T7-B)") (class "Default")
      (node (ref "C14") (pin "2") (pinfunction "2_2") (pintype "passive"))
      (node (ref "D5") (pin "A") (pinfunction "A_A") (pintype "passive"))
      (node (ref "R23") (pin "1") (pinfunction "1_1") (pintype "passive"))
      (node (ref "T7") (pin "2") (pinfunction "B_2") (pintype "passive"))
    )
    (net (code "49") (name "Net-(T7-C)") (class "Default")
      (node (ref "C14") (pin "1") (pinfunction "1_1") (pintype "passive"))
      (node (ref "R21") (pin "2") (pinfunction "2_2") (pintype "passive"))
      (node (ref "T7") (pin "1") (pinfunction "C_1") (pintype "passive"))
    )
    (net (code "50") (name "Net-(T8-E)") (class "Default")
      (node (ref "C18*") (pin "1") (pinfunction "1_1") (pintype "passive"))
      (node (ref "R24") (pin "2") (pinfunction "2_2") (pintype "passive"))
      (node (ref "T8") (pin "1") (pinfunction "E_1") (pintype "passive"))
      (node (ref "T9") (pin "1") (pinfunction "B_1") (pintype "passive"))
    )
    (net (code "51") (name "Net-(T9-E)") (class "Default")
      (node (ref "R25") (pin "2") (pinfunction "2_2") (pintype "passive"))
      (node (ref "R26") (pin "1") (pinfunction "1_1") (pintype "passive"))
      (node (ref "T9") (pin "3") (pinfunction "E_3") (pintype "passive"))
    )
    (net (code "52") (name "Net-(T14-E)") (class "Default")
      (node (ref "R216") (pin "1") (pinfunction "1_1") (pintype "passive"))
      (node (ref "T14") (pin "3") (pinfunction "E_3") (pintype "passive"))
      (node (ref "T15") (pin "3") (pinfunction "B_3") (pintype "passive"))
    )
    (net (code "53") (name "Net-(T15-C)") (class "Default")
      (node (ref "C13") (pin "2") (pinfunction "2_2") (pintype "passive"))
      (node (ref "C211") (pin "2") (pinfunction "2_2") (pintype "passive"))
      (node (ref "D10") (pin "C") (pinfunction "C_C") (pintype "passive"))
      (node (ref "D12") (pin "C") (pinfunction "C_C") (pintype "passive"))
      (node (ref "R219") (pin "1") (pinfunction "1_1") (pintype "passive"))
      (node (ref "T15") (pin "2") (pinfunction "C_2") (pintype "passive"))
      (node (ref "T206") (pin "1") (pinfunction "E_1") (pintype "passive"))
      (node (ref "T218") (pin "3") (pinfunction "B_3") (pintype "passive"))
      (node (ref "T6") (pin "1") (pinfunction "C_1") (pintype "passive"))
    )
    (net (code "54") (name "Net-(T15-E)") (class "Default")
      (node (ref "R207") (pin "2") (pinfunction "2_2") (pintype "passive"))
      (node (ref "T15") (pin "1") (pinfunction "E_1") (pintype "passive"))
      (node (ref "T203") (pin "1") (pinfunction "C_1") (pintype "passive"))
    )
    (net (code "55") (name "Net-(T201-B)") (class "Default")
      (node (ref "D8") (pin "A") (pinfunction "A_A") (pintype "passive"))
      (node (ref "R214") (pin "2") (pinfunction "2_2") (pintype "passive"))
      (node (ref "T201") (pin "2") (pinfunction "B_2") (pintype "passive"))
    )
    (net (code "56") (name "Net-(T201-C)") (class "Default")
      (node (ref "R210") (pin "1") (pinfunction "1_1") (pintype "passive"))
      (node (ref "R211") (pin "1") (pinfunction "1_1") (pintype "passive"))
      (node (ref "T201") (pin "1") (pinfunction "C_1") (pintype "passive"))
    )
    (net (code "57") (name "Net-(T201-E)") (class "Default")
      (node (ref "R213") (pin "2") (pinfunction "2_2") (pintype "passive"))
      (node (ref "T201") (pin "3") (pinfunction "E_3") (pintype "passive"))
    )
    (net (code "58") (name "Net-(T202-B)") (class "Default")
      (node (ref "R209") (pin "2") (pinfunction "2_2") (pintype "passive"))
      (node (ref "T202") (pin "2") (pinfunction "B_2") (pintype "passive"))
    )
    (net (code "59") (name "Net-(T202-C)") (class "Default")
      (node (ref "C210") (pin "1") (pinfunction "1_1") (pintype "passive"))
      (node (ref "C211") (pin "1") (pinfunction "1_1") (pintype "passive"))
      (node (ref "D10") (pin "A") (pinfunction "A_A") (pintype "passive"))
      (node (ref "LED2") (pin "A") (pinfunction "A_A") (pintype "passive"))
      (node (ref "T202") (pin "1") (pinfunction "C_1") (pintype "passive"))
    )
    (net (code "60") (name "Net-(T202-E)") (class "Default")
      (node (ref "R210") (pin "2") (pinfunction "2_2") (pintype "passive"))
      (node (ref "T202") (pin "3") (pinfunction "E_3") (pintype "passive"))
    )
    (net (code "61") (name "Net-(T203-B)") (class "Default")
      (node (ref "R212") (pin "2") (pinfunction "2_2") (pintype "passive"))
      (node (ref "T203") (pin "2") (pinfunction "B_2") (pintype "passive"))
    )
    (net (code "62") (name "Net-(T203-E)") (class "Default")
      (node (ref "R211") (pin "2") (pinfunction "2_2") (pintype "passive"))
      (node (ref "T203") (pin "3") (pinfunction "E_3") (pintype "passive"))
    )
    (net (code "63") (name "Net-(T206-B)") (class "Default")
      (node (ref "R19") (pin "2") (pinfunction "2_2") (pintype "passive"))
      (node (ref "R219") (pin "2") (pinfunction "2_2") (pintype "passive"))
      (node (ref "T206") (pin "3") (pinfunction "B_3") (pintype "passive"))
    )
    (net (code "64") (name "Net-(T206-C)") (class "Default")
      (node (ref "R20") (pin "1") (pinfunction "1_1") (pintype "passive"))
      (node (ref "T206") (pin "2") (pinfunction "C_2") (pintype "passive"))
      (node (ref "T6") (pin "2") (pinfunction "B_2") (pintype "passive"))
    )
    (net (code "65") (name "Net-(T217-B)") (class "Default")
      (node (ref "C214") (pin "2") (pinfunction "2_2") (pintype "passive"))
      (node (ref "D3") (pin "C") (pinfunction "C_C") (pintype "passive"))
      (node (ref "R223") (pin "2") (pinfunction "2_2") (pintype "passive"))
      (node (ref "T217") (pin "2") (pinfunction "B_2") (pintype "passive"))
    )
    (net (code "66") (name "Net-(T217-C)") (class "Default")
      (node (ref "C214") (pin "1") (pinfunction "1_1") (pintype "passive"))
      (node (ref "R221") (pin "2") (pinfunction "2_2") (pintype "passive"))
      (node (ref "T217") (pin "1") (pinfunction "C_1") (pintype "passive"))
    )
    (net (code "67") (name "Net-(T217-E)") (class "Default")
      (node (ref "CIEVKA") (pin "1") (pinfunction "1_1") (pintype "passive"))
      (node (ref "D20") (pin "A") (pinfunction "A_A") (pintype "passive"))
      (node (ref "D21") (pin "K") (pinfunction "K_K") (pintype "passive"))
      (node (ref "R18") (pin "2") (pinfunction "2_2") (pintype "passive"))
      (node (ref "R225") (pin "2") (pinfunction "2_2") (pintype "passive"))
      (node (ref "R227") (pin "2") (pinfunction "2_2") (pintype "passive"))
      (node (ref "R228") (pin "2") (pinfunction "2_2") (pintype "passive"))
      (node (ref "R229") (pin "2") (pinfunction "2_2") (pintype "passive"))
      (node (ref "R230") (pin "2") (pinfunction "2_2") (pintype "passive"))
      (node (ref "R231") (pin "2") (pinfunction "2_2") (pintype "passive"))
      (node (ref "R232") (pin "2") (pinfunction "2_2") (pintype "passive"))
      (node (ref "R233") (pin "2") (pinfunction "2_2") (pintype "passive"))
      (node (ref "R234") (pin "2") (pinfunction "2_2") (pintype "passive"))
      (node (ref "R25") (pin "1") (pinfunction "1_1") (pintype "passive"))
      (node (ref "R27") (pin "1") (pinfunction "1_1") (pintype "passive"))
      (node (ref "R28") (pin "1") (pinfunction "1_1") (pintype "passive"))
      (node (ref "R29") (pin "1") (pinfunction "1_1") (pintype "passive"))
      (node (ref "R30") (pin "1") (pinfunction "1_1") (pintype "passive"))
      (node (ref "R31") (pin "1") (pinfunction "1_1") (pintype "passive"))
      (node (ref "R32") (pin "1") (pinfunction "1_1") (pintype "passive"))
      (node (ref "R33") (pin "1") (pinfunction "1_1") (pintype "passive"))
      (node (ref "R34") (pin "1") (pinfunction "1_1") (pintype "passive"))
      (node (ref "R35") (pin "1") (pinfunction "1_1") (pintype "passive"))
      (node (ref "R36") (pin "1") (pinfunction "1_1") (pintype "passive"))
      (node (ref "R37") (pin "2") (pinfunction "2_2") (pintype "passive"))
      (node (ref "R38") (pin "2") (pinfunction "2_2") (pintype "passive"))
      (node (ref "R39") (pin "2") (pinfunction "2_2") (pintype "passive"))
      (node (ref "R40") (pin "2") (pinfunction "2_2") (pintype "passive"))
      (node (ref "R41") (pin "1") (pinfunction "1_1") (pintype "passive"))
      (node (ref "R42") (pin "1") (pinfunction "1_1") (pintype "passive"))
      (node (ref "T217") (pin "3") (pinfunction "E_3") (pintype "passive"))
      (node (ref "T7") (pin "3") (pinfunction "E_3") (pintype "passive"))
    )
    (net (code "68") (name "Net-(T218-E)") (class "Default")
      (node (ref "C218*") (pin "1") (pinfunction "1_1") (pintype "passive"))
      (node (ref "R224") (pin "1") (pinfunction "1_1") (pintype "passive"))
      (node (ref "T218") (pin "1") (pinfunction "E_1") (pintype "passive"))
      (node (ref "T219") (pin "1") (pinfunction "B_1") (pintype "passive"))
    )
    (net (code "69") (name "Net-(T219-E)") (class "Default")
      (node (ref "R225") (pin "1") (pinfunction "1_1") (pintype "passive"))
      (node (ref "R226") (pin "2") (pinfunction "2_2") (pintype "passive"))
      (node (ref "T219") (pin "3") (pinfunction "E_3") (pintype "passive"))
    )
    (net (code "70") (name "unconnected-(C9-C_EL+-PadC+)") (class "Default")
      (node (ref "C9") (pin "C+") (pinfunction "C_EL+_C+") (pintype "passive"))
    )
  )
)
